# PSU.net
KiCad netlist of a schematic drawn in Altium Designer
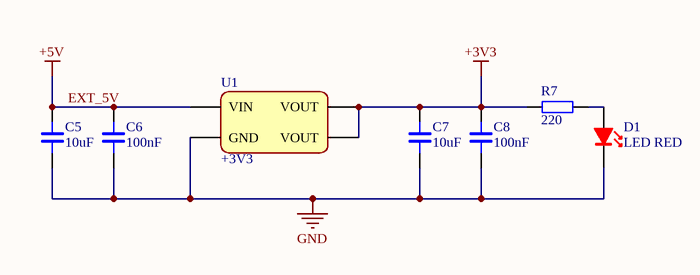
[diagram p0: PSU.SchDoc]

(export (version "E")
  (design (tool "Eeschema 10.0.6"))
  (components
    (comp (ref "C5")
      (value "10uF")
      (footprint "CAP_0603")
      (description "0603 Multilayer Ceramic Capacitors MLCC - SMD/SMT ROHS")
      (fields (field (name "LCSC PART") "?"))
      (libsource (lib "FIC_OAL") (part "CAP_0603"))
    )
    (comp (ref "C6")
      (value "100nF")
      (footprint "CAP_0603")
      (description "0603 Multilayer Ceramic Capacitors MLCC - SMD/SMT ROHS")
      (fields (field (name "LCSC PART") "?"))
      (libsource (lib "FIC_OAL") (part "CAP_0603"))
    )
    (comp (ref "C7")
      (value "10uF")
      (footprint "CAP_0603")
      (description "0603 Multilayer Ceramic Capacitors MLCC - SMD/SMT ROHS")
      (fields (field (name "LCSC PART") "?"))
      (libsource (lib "FIC_OAL") (part "CAP_0603"))
    )
    (comp (ref "C8")
      (value "100nF")
      (footprint "CAP_0603")
      (description "0603 Multilayer Ceramic Capacitors MLCC - SMD/SMT ROHS")
      (fields (field (name "LCSC PART") "?"))
      (libsource (lib "FIC_OAL") (part "CAP_0603"))
    )
    (comp (ref "D1")
      (value "LED RED")
      (footprint "LED_RED_V0805")
      (description "20mA 615nm~630nm RED")
      (fields (field (name "JLCPCB PART") "?"))
      (libsource (lib "FIC_OAL") (part "LED_RED_V0805"))
    )
    (comp (ref "R7")
      (value "220")
      (footprint "RES_0603")
      (description "0603 Thick Film Resistor - Surface Mount ROHS")
      (fields (field (name "MFR. PART") "?"))
      (libsource (lib "FIC_OAL") (part "RES_0603"))
    )
    (comp (ref "U1")
      (value "+3V3")
      (footprint "PWR_LD1117_SOT223")
      (description "Linear Voltage Regulators (LDO)")
      (fields (field (name "MRF. PART") "?"))
      (libsource (lib "FIC_OAL") (part "PWR_LD1117"))
    )
  )
  (nets
    (net (code "1") (name "+3V3") (class "Default")
      (node (ref "C7") (pin "2") (pinfunction "2_2") (pintype "passive"))
      (node (ref "C8") (pin "2") (pinfunction "2_2") (pintype "passive"))
      (node (ref "R7") (pin "1") (pinfunction "1_1") (pintype "passive"))
      (node (ref "U1") (pin "2") (pinfunction "_VOUT_2") (pintype "passive"))
      (node (ref "U1") (pin "4") (pinfunction "VOUT_4") (pintype "passive"))
    )
    (net (code "2") (name "+5V") (class "Default")
      (node (ref "C5") (pin "2") (pinfunction "2_2") (pintype "passive"))
      (node (ref "C6") (pin "2") (pinfunction "2_2") (pintype "passive"))
      (node (ref "U1") (pin "3") (pinfunction "VIN_3") (pintype "passive"))
    )
    (net (code "3") (name "GND") (class "Default")
      (node (ref "C5") (pin "1") (pinfunction "1_1") (pintype "passive"))
      (node (ref "C6") (pin "1") (pinfunction "1_1") (pintype "passive"))
      (node (ref "C7") (pin "1") (pinfunction "1_1") (pintype "passive"))
      (node (ref "C8") (pin "1") (pinfunction "1_1") (pintype "passive"))
      (node (ref "D1") (pin "C") (pinfunction "1_C") (pintype "passive"))
      (node (ref "U1") (pin "1") (pinfunction "GND_1") (pintype "passive"))
    )
    (net (code "4") (name "Net-(D1-2)") (class "Default")
      (node (ref "D1") (pin "A") (pinfunction "2_A") (pintype "passive"))
      (node (ref "R7") (pin "2") (pinfunction "2_2") (pintype "passive"))
    )
  )
)
